# 20A_3V3_EVB.net
KiCad netlist of a schematic drawn in Altium Designer
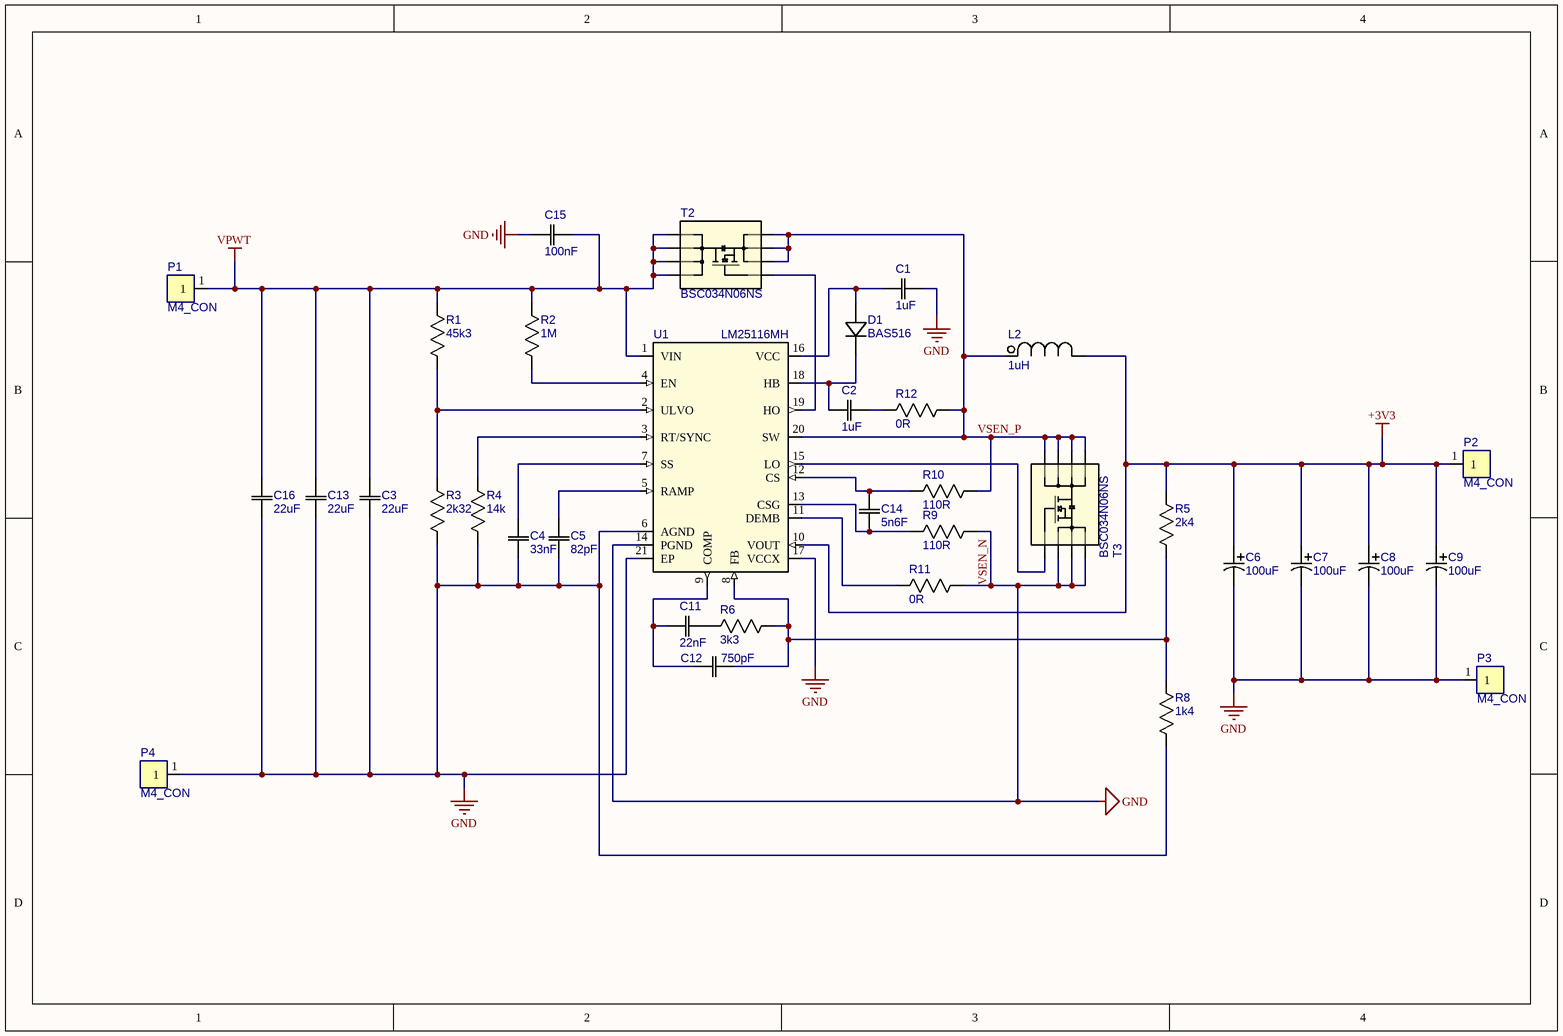
[diagram p0: 20A_3V3_EVB.SchDoc]

(export (version "E")
  (design (tool "Eeschema 10.0.6"))
  (components
    (comp (ref "C1")
      (value "1uF")
      (footprint "C0603")
      (description "0603 1UF 16V 10% 105K X5R")
      (fields (field (name "MFR.") "OUDEIBUN"))
      (libsource (lib "C0603") (part "OUDEIBUN_1uF"))
    )
    (comp (ref "C2")
      (value "1uF")
      (footprint "C0603")
      (description "0603 1UF 16V 10% 105K X5R")
      (fields (field (name "MFR.") "OUDEIBUN"))
      (libsource (lib "C0603") (part "OUDEIBUN_1uF"))
    )
    (comp (ref "C3")
      (value "22uF")
      (footprint "1210")
      (description "1210 22UF 226K 100V X7R")
      (fields (field (name "MFR.") "OUBEIDUN"))
      (libsource (lib "C1210") (part "OUBEIDUN_226K_X7R_100V"))
    )
    (comp (ref "C4")
      (value "33nF")
      (footprint "0402")
      (description "0402 33nF 333K 16V X7R")
      (fields (field (name "MFR.") "OBEIDUN"))
      (libsource (lib "C0402") (part "OBEIDUN_33nF"))
    )
    (comp (ref "C5")
      (value "82pF")
      (footprint "0402")
      (description "82pF 50V C0G CL05C820JB5NNNC")
      (fields (field (name "MFR.") "Samsung"))
      (libsource (lib "C0402") (part "taobao_82pF"))
    )
    (comp (ref "C6")
      (value "100uF")
      (footprint "3528")
      (description "6TPE100MAZB 6.3V 100uF ESR 25mR")
      (fields (field (name "MFR.") "Auwah"))
      (libsource (lib "C3528") (part "6TPE100MPB"))
    )
    (comp (ref "C7")
      (value "100uF")
      (footprint "3528")
      (description "6TPE100MAZB 6.3V 100uF ESR 25mR")
      (fields (field (name "MFR.") "Auwah"))
      (libsource (lib "C3528") (part "6TPE100MPB"))
    )
    (comp (ref "C8")
      (value "100uF")
      (footprint "3528")
      (description "6TPE100MAZB 6.3V 100uF ESR 25mR")
      (fields (field (name "MFR.") "Auwah"))
      (libsource (lib "C3528") (part "6TPE100MPB"))
    )
    (comp (ref "C9")
      (value "100uF")
      (footprint "3528")
      (description "6TPE100MAZB 6.3V 100uF ESR 25mR")
      (fields (field (name "MFR.") "Auwah"))
      (libsource (lib "C3528") (part "6TPE100MPB"))
    )
    (comp (ref "C11")
      (value "22nF")
      (footprint "0402")
      (description "0402 33nF 333K 16V X7R")
      (fields (field (name "MFR.") "OBEIDUN"))
      (libsource (lib "C0402") (part "OBEIDUN_33nF"))
    )
    (comp (ref "C12")
      (value "750pF")
      (footprint "CAP_CC0402_YAG")
      (description "GCM1555C1H330JA16J")
      (fields (field (name "MFR.") "Murata Electronics"))
      (libsource (lib "C0402") (part "GCM1555C1H330JA16J"))
    )
    (comp (ref "C13")
      (value "22uF")
      (footprint "1210")
      (description "1210 22UF 226K 100V X7R")
      (fields (field (name "MFR.") "OUBEIDUN"))
      (libsource (lib "C1210") (part "OUBEIDUN_226K_X7R_100V"))
    )
    (comp (ref "C14")
      (value "5n6F")
      (footprint "0402")
      (description "0402 562K 5.6NF 50V X7R")
      (fields (field (name "MFR.") "OBEIDUN"))
      (libsource (lib "C0402") (part "OBEIDUN_5n6F"))
    )
    (comp (ref "C15")
      (value "100nF")
      (footprint "C0603")
      (description "0603 100NF 50V 10% 104K X7R")
      (fields (field (name "MFR.") "OUDEIBUN"))
      (libsource (lib "C0603") (part "OUDEIBUN_100nF"))
    )
    (comp (ref "C16")
      (value "22uF")
      (footprint "1210")
      (description "1210 22UF 226K 100V X7R")
      (fields (field (name "MFR.") "OUBEIDUN"))
      (libsource (lib "C1210") (part "OUBEIDUN_226K_X7R_100V"))
    )
    (comp (ref "D1")
      (value "BAS516")
      (footprint "SOD-523")
      (description "SOD-523 100V/250mA")
      (fields (field (name "MFR.") "OBEIDUN"))
      (libsource (lib "BAS516") (part "OBEIDUN_BAS516"))
    )
    (comp (ref "L2")
      (value "1uH")
      (footprint "XAL1010")
      (description "1uH Shld 20% 43.5A 1.1mOhms")
      (fields (field (name "MFR.") "Coilcraft"))
      (libsource (lib "XAL1010") (part "XAL1010-102MEB"))
    )
    (comp (ref "P1")
      (value "M4_CON")
      (footprint "PCBComponent_1")
      (fields (field (name "MFR.") "LFX"))
      (libsource (lib "") (part "M4_CON_1"))
    )
    (comp (ref "P2")
      (value "M4_CON")
      (footprint "PCBComponent_1")
      (fields (field (name "MFR.") "LFX"))
      (libsource (lib "M4_CON") (part "M4_CON"))
    )
    (comp (ref "P3")
      (value "M4_CON")
      (footprint "PCBComponent_1")
      (fields (field (name "MFR.") "LFX"))
      (libsource (lib "M4_CON") (part "M4_CON"))
    )
    (comp (ref "P4")
      (value "M4_CON")
      (footprint "PCBComponent_1")
      (fields (field (name "MFR.") "LFX"))
      (libsource (lib "") (part "M4_CON_1"))
    )
    (comp (ref "R1")
      (value "45k3")
      (footprint "0402_PAN")
      (description "RC0402FR-070RL\r\nThick Film Resistors - SMD 0 Ohms 62.5mW 0402 1%")
      (fields (field (name "MFR.") "YAGEO"))
      (libsource (lib "R0402") (part "RC0402FR-070RL"))
    )
    (comp (ref "R2")
      (value "1M")
      (footprint "0402")
      (description "OUDEIBUN\r\n1% 1M")
      (fields (field (name "MFR.") "OUDEIBUN"))
      (libsource (lib "R0402") (part "OUDEIBUN_1M"))
    )
    (comp (ref "R3")
      (value "2k32")
      (footprint "0402_PAN")
      (description "RC0402FR-070RL\r\nThick Film Resistors - SMD 0 Ohms 62.5mW 0402 1%")
      (fields (field (name "MFR.") "YAGEO"))
      (libsource (lib "R0402") (part "RC0402FR-070RL"))
    )
    (comp (ref "R4")
      (value "14k")
      (footprint "0402_PAN")
      (description "RT0402FRE0715KL\r\nSMD 1/16W 15K ohm 1% 50ppm")
      (fields (field (name "MFR.") "YAGEO"))
      (libsource (lib "R0402") (part "RT0402FRE0715KL"))
    )
    (comp (ref "R5")
      (value "2k4")
      (footprint "0402")
      (description "OUDEIBUN\r\n1% 2k4")
      (fields (field (name "MFR.") "OUDEIBUN"))
      (libsource (lib "R0402") (part "OUDEIBUN_2k4"))
    )
    (comp (ref "R6")
      (value "3k3")
      (footprint "0402_PAN")
      (description "Thick Film Resistors - SMD 57.6 kOhms 62.5mW 0402 1%")
      (libsource (lib "R0402") (part "RC0402FR-0757K6L"))
    )
    (comp (ref "R8")
      (value "1k4")
      (footprint "0402_PAN")
      (description "RC0402FR-070RL\r\nThick Film Resistors - SMD 0 Ohms 62.5mW 0402 1%")
      (fields (field (name "MFR.") "YAGEO"))
      (libsource (lib "R0402") (part "RC0402FR-070RL"))
    )
    (comp (ref "R9")
      (value "110R")
      (footprint "0402_PAN")
      (description "0R ±1% 1/16W")
      (fields (field (name "MFR.") "UNIOHM"))
      (libsource (lib "R0402") (part "0402WGF0000TCE"))
    )
    (comp (ref "R10")
      (value "110R")
      (footprint "0402_PAN")
      (description "0R ±1% 1/16W")
      (fields (field (name "MFR.") "UNIOHM"))
      (libsource (lib "R0402") (part "0402WGF0000TCE"))
    )
    (comp (ref "R11")
      (value "0R")
      (footprint "0402")
      (description "OUDEIBUN\r\n0R 1% 1/16W")
      (fields (field (name "MFR.") "OUDEIBUN"))
      (libsource (lib "R0402") (part "OUDEIBUN_0R"))
    )
    (comp (ref "R12")
      (value "0R")
      (footprint "0402")
      (description "OUDEIBUN\r\n0R 1% 1/16W")
      (fields (field (name "MFR.") "OUDEIBUN"))
      (libsource (lib "R0402") (part "OUDEIBUN_0R"))
    )
    (comp (ref "T2")
      (value "BSC034N06NS")
      (footprint "PQFNWB5x6")
      (description "MPower Transistor, 60V")
      (fields (field (name "MFR.") "Infineon Technologies"))
      (libsource (lib "MOS_PQFNWB5x6") (part "BSC034N06NS"))
    )
    (comp (ref "T3")
      (value "BSC034N06NS")
      (footprint "PQFNWB5x6")
      (description "MPower Transistor, 60V")
      (fields (field (name "MFR.") "Infineon Technologies"))
      (libsource (lib "") (part "BSC034N06NS_1"))
    )
    (comp (ref "U1")
      (value "LM25116MH")
      (footprint "20-HTSSOP")
      (description "Switching Controllers WIDE RANGE SYNC BUCK CONTROLLER")
      (fields (field (name "MFR.") "Texas Instruments"))
      (libsource (lib "LM25116MH") (part "LM25116MH"))
    )
  )
  (nets
    (net (code "1") (name "+3V3") (class "Default")
      (node (ref "C6") (pin "1") (pinfunction "1_1") (pintype "passive"))
      (node (ref "C7") (pin "1") (pinfunction "1_1") (pintype "passive"))
      (node (ref "C8") (pin "1") (pinfunction "1_1") (pintype "passive"))
      (node (ref "C9") (pin "1") (pinfunction "1_1") (pintype "passive"))
      (node (ref "L2") (pin "2") (pinfunction "2_2") (pintype "passive"))
      (node (ref "P2") (pin "1") (pinfunction "1_1") (pintype "passive"))
      (node (ref "R5") (pin "1") (pinfunction "1_1") (pintype "passive"))
      (node (ref "U1") (pin "10") (pinfunction "VOUT_10") (pintype "input"))
    )
    (net (code "2") (name "/VSEN_P") (class "Default")
      (node (ref "L2") (pin "1") (pinfunction "1_1") (pintype "passive"))
      (node (ref "R10") (pin "2") (pinfunction "2_2") (pintype "passive"))
      (node (ref "R12") (pin "2") (pinfunction "2_2") (pintype "passive"))
      (node (ref "T2") (pin "1") (pinfunction "1_1") (pintype "passive"))
      (node (ref "T2") (pin "2") (pinfunction "2_2") (pintype "passive"))
      (node (ref "T2") (pin "3") (pinfunction "3_3") (pintype "passive"))
      (node (ref "T3") (pin "5") (pinfunction "5_5") (pintype "passive"))
      (node (ref "T3") (pin "6") (pinfunction "6_6") (pintype "passive"))
      (node (ref "T3") (pin "7") (pinfunction "7_7") (pintype "passive"))
      (node (ref "T3") (pin "8") (pinfunction "8_8") (pintype "passive"))
      (node (ref "U1") (pin "20") (pinfunction "SW_20") (pintype "power_in"))
    )
    (net (code "3") (name "GND") (class "Default")
      (node (ref "C1") (pin "1") (pinfunction "1_1") (pintype "passive"))
      (node (ref "C13") (pin "1") (pinfunction "11_1") (pintype "passive"))
      (node (ref "C15") (pin "2") (pinfunction "2_2") (pintype "passive"))
      (node (ref "C16") (pin "1") (pinfunction "11_1") (pintype "passive"))
      (node (ref "C3") (pin "1") (pinfunction "11_1") (pintype "passive"))
      (node (ref "C4") (pin "1") (pinfunction "1_1") (pintype "passive"))
      (node (ref "C5") (pin "1") (pinfunction "1_1") (pintype "passive"))
      (node (ref "C6") (pin "2") (pinfunction "2_2") (pintype "passive"))
      (node (ref "C7") (pin "2") (pinfunction "2_2") (pintype "passive"))
      (node (ref "C8") (pin "2") (pinfunction "2_2") (pintype "passive"))
      (node (ref "C9") (pin "2") (pinfunction "2_2") (pintype "passive"))
      (node (ref "P3") (pin "1") (pinfunction "1_1") (pintype "passive"))
      (node (ref "P4") (pin "1") (pinfunction "1_1") (pintype "passive"))
      (node (ref "R11") (pin "2") (pinfunction "2_2") (pintype "passive"))
      (node (ref "R3") (pin "1") (pinfunction "1_1") (pintype "passive"))
      (node (ref "R4") (pin "1") (pinfunction "1_1") (pintype "passive"))
      (node (ref "R8") (pin "2") (pinfunction "2_2") (pintype "passive"))
      (node (ref "R9") (pin "2") (pinfunction "2_2") (pintype "passive"))
      (node (ref "T3") (pin "1") (pinfunction "1_1") (pintype "passive"))
      (node (ref "T3") (pin "2") (pinfunction "2_2") (pintype "passive"))
      (node (ref "T3") (pin "3") (pinfunction "3_3") (pintype "passive"))
      (node (ref "U1") (pin "14") (pinfunction "PGND_14") (pintype "power_in"))
      (node (ref "U1") (pin "17") (pinfunction "VCCX_17") (pintype "power_in"))
      (node (ref "U1") (pin "21") (pinfunction "EP_21") (pintype "power_in"))
      (node (ref "U1") (pin "6") (pinfunction "AGND_6") (pintype "power_in"))
    )
    (net (code "4") (name "Net-(C2-Pad1)") (class "Default")
      (node (ref "C2") (pin "1") (pinfunction "1_1") (pintype "passive"))
      (node (ref "R12") (pin "1") (pinfunction "1_1") (pintype "passive"))
    )
    (net (code "5") (name "Net-(C11-Pad1)") (class "Default")
      (node (ref "C11") (pin "1") (pinfunction "1_1") (pintype "passive"))
      (node (ref "R6") (pin "2") (pinfunction "2_2") (pintype "passive"))
    )
    (net (code "6") (name "Net-(U1-COMP)") (class "Default")
      (node (ref "C11") (pin "2") (pinfunction "2_2") (pintype "passive"))
      (node (ref "C12") (pin "2") (pinfunction "2_2") (pintype "passive"))
      (node (ref "U1") (pin "9") (pinfunction "COMP_9") (pintype "output"))
    )
    (net (code "7") (name "Net-(U1-CS)") (class "Default")
      (node (ref "C14") (pin "1") (pinfunction "1_1") (pintype "passive"))
      (node (ref "R10") (pin "1") (pinfunction "1_1") (pintype "passive"))
      (node (ref "U1") (pin "12") (pinfunction "CS_12") (pintype "input"))
    )
    (net (code "8") (name "Net-(U1-CSG)") (class "Default")
      (node (ref "C14") (pin "2") (pinfunction "2_2") (pintype "passive"))
      (node (ref "R9") (pin "1") (pinfunction "1_1") (pintype "passive"))
      (node (ref "U1") (pin "13") (pinfunction "CSG_13") (pintype "passive"))
    )
    (net (code "9") (name "Net-(U1-DEMB)") (class "Default")
      (node (ref "R11") (pin "1") (pinfunction "1_1") (pintype "passive"))
      (node (ref "U1") (pin "11") (pinfunction "DEMB_11") (pintype "passive"))
    )
    (net (code "10") (name "Net-(U1-EN)") (class "Default")
      (node (ref "R2") (pin "1") (pinfunction "1_1") (pintype "passive"))
      (node (ref "U1") (pin "4") (pinfunction "EN_4") (pintype "input"))
    )
    (net (code "11") (name "Net-(U1-FB)") (class "Default")
      (node (ref "C12") (pin "1") (pinfunction "1_1") (pintype "passive"))
      (node (ref "R5") (pin "2") (pinfunction "2_2") (pintype "passive"))
      (node (ref "R6") (pin "1") (pinfunction "1_1") (pintype "passive"))
      (node (ref "R8") (pin "1") (pinfunction "1_1") (pintype "passive"))
      (node (ref "U1") (pin "8") (pinfunction "FB_8") (pintype "input"))
    )
    (net (code "12") (name "Net-(U1-HB)") (class "Default")
      (node (ref "C2") (pin "2") (pinfunction "2_2") (pintype "passive"))
      (node (ref "D1") (pin "1") (pinfunction "1_1") (pintype "passive"))
      (node (ref "U1") (pin "18") (pinfunction "HB_18") (pintype "passive"))
    )
    (net (code "13") (name "Net-(U1-HO)") (class "Default")
      (node (ref "T2") (pin "4") (pinfunction "4_4") (pintype "passive"))
      (node (ref "U1") (pin "19") (pinfunction "HO_19") (pintype "output"))
    )
    (net (code "14") (name "Net-(U1-LO)") (class "Default")
      (node (ref "T3") (pin "4") (pinfunction "4_4") (pintype "passive"))
      (node (ref "U1") (pin "15") (pinfunction "LO_15") (pintype "output"))
    )
    (net (code "15") (name "Net-(U1-RAMP)") (class "Default")
      (node (ref "C5") (pin "2") (pinfunction "2_2") (pintype "passive"))
      (node (ref "U1") (pin "5") (pinfunction "RAMP_5") (pintype "input"))
    )
    (net (code "16") (name "Net-(U1-RT{slash}SYNC)") (class "Default")
      (node (ref "R4") (pin "2") (pinfunction "2_2") (pintype "passive"))
      (node (ref "U1") (pin "3") (pinfunction "RT/SYNC_3") (pintype "input"))
    )
    (net (code "17") (name "Net-(U1-SS)") (class "Default")
      (node (ref "C4") (pin "2") (pinfunction "2_2") (pintype "passive"))
      (node (ref "U1") (pin "7") (pinfunction "SS_7") (pintype "input"))
    )
    (net (code "18") (name "Net-(U1-ULVO)") (class "Default")
      (node (ref "R1") (pin "1") (pinfunction "1_1") (pintype "passive"))
      (node (ref "R3") (pin "2") (pinfunction "2_2") (pintype "passive"))
      (node (ref "U1") (pin "2") (pinfunction "ULVO_2") (pintype "input"))
    )
    (net (code "19") (name "Net-(U1-VCC)") (class "Default")
      (node (ref "C1") (pin "2") (pinfunction "2_2") (pintype "passive"))
      (node (ref "D1") (pin "2") (pinfunction "2_2") (pintype "passive"))
      (node (ref "U1") (pin "16") (pinfunction "VCC_16") (pintype "power_in"))
    )
    (net (code "20") (name "VPWT") (class "Default")
      (node (ref "C13") (pin "2") (pinfunction "12_2") (pintype "passive"))
      (node (ref "C15") (pin "1") (pinfunction "1_1") (pintype "passive"))
      (node (ref "C16") (pin "2") (pinfunction "12_2") (pintype "passive"))
      (node (ref "C3") (pin "2") (pinfunction "12_2") (pintype "passive"))
      (node (ref "P1") (pin "1") (pinfunction "1_1") (pintype "passive"))
      (node (ref "R1") (pin "2") (pinfunction "2_2") (pintype "passive"))
      (node (ref "R2") (pin "2") (pinfunction "2_2") (pintype "passive"))
      (node (ref "T2") (pin "5") (pinfunction "5_5") (pintype "passive"))
      (node (ref "T2") (pin "6") (pinfunction "6_6") (pintype "passive"))
      (node (ref "T2") (pin "7") (pinfunction "7_7") (pintype "passive"))
      (node (ref "T2") (pin "8") (pinfunction "8_8") (pintype "passive"))
      (node (ref "U1") (pin "1") (pinfunction "VIN_1") (pintype "power_in"))
    )
  )
)
